# powermeting.net
KiCad netlist of a schematic drawn in EAGLE
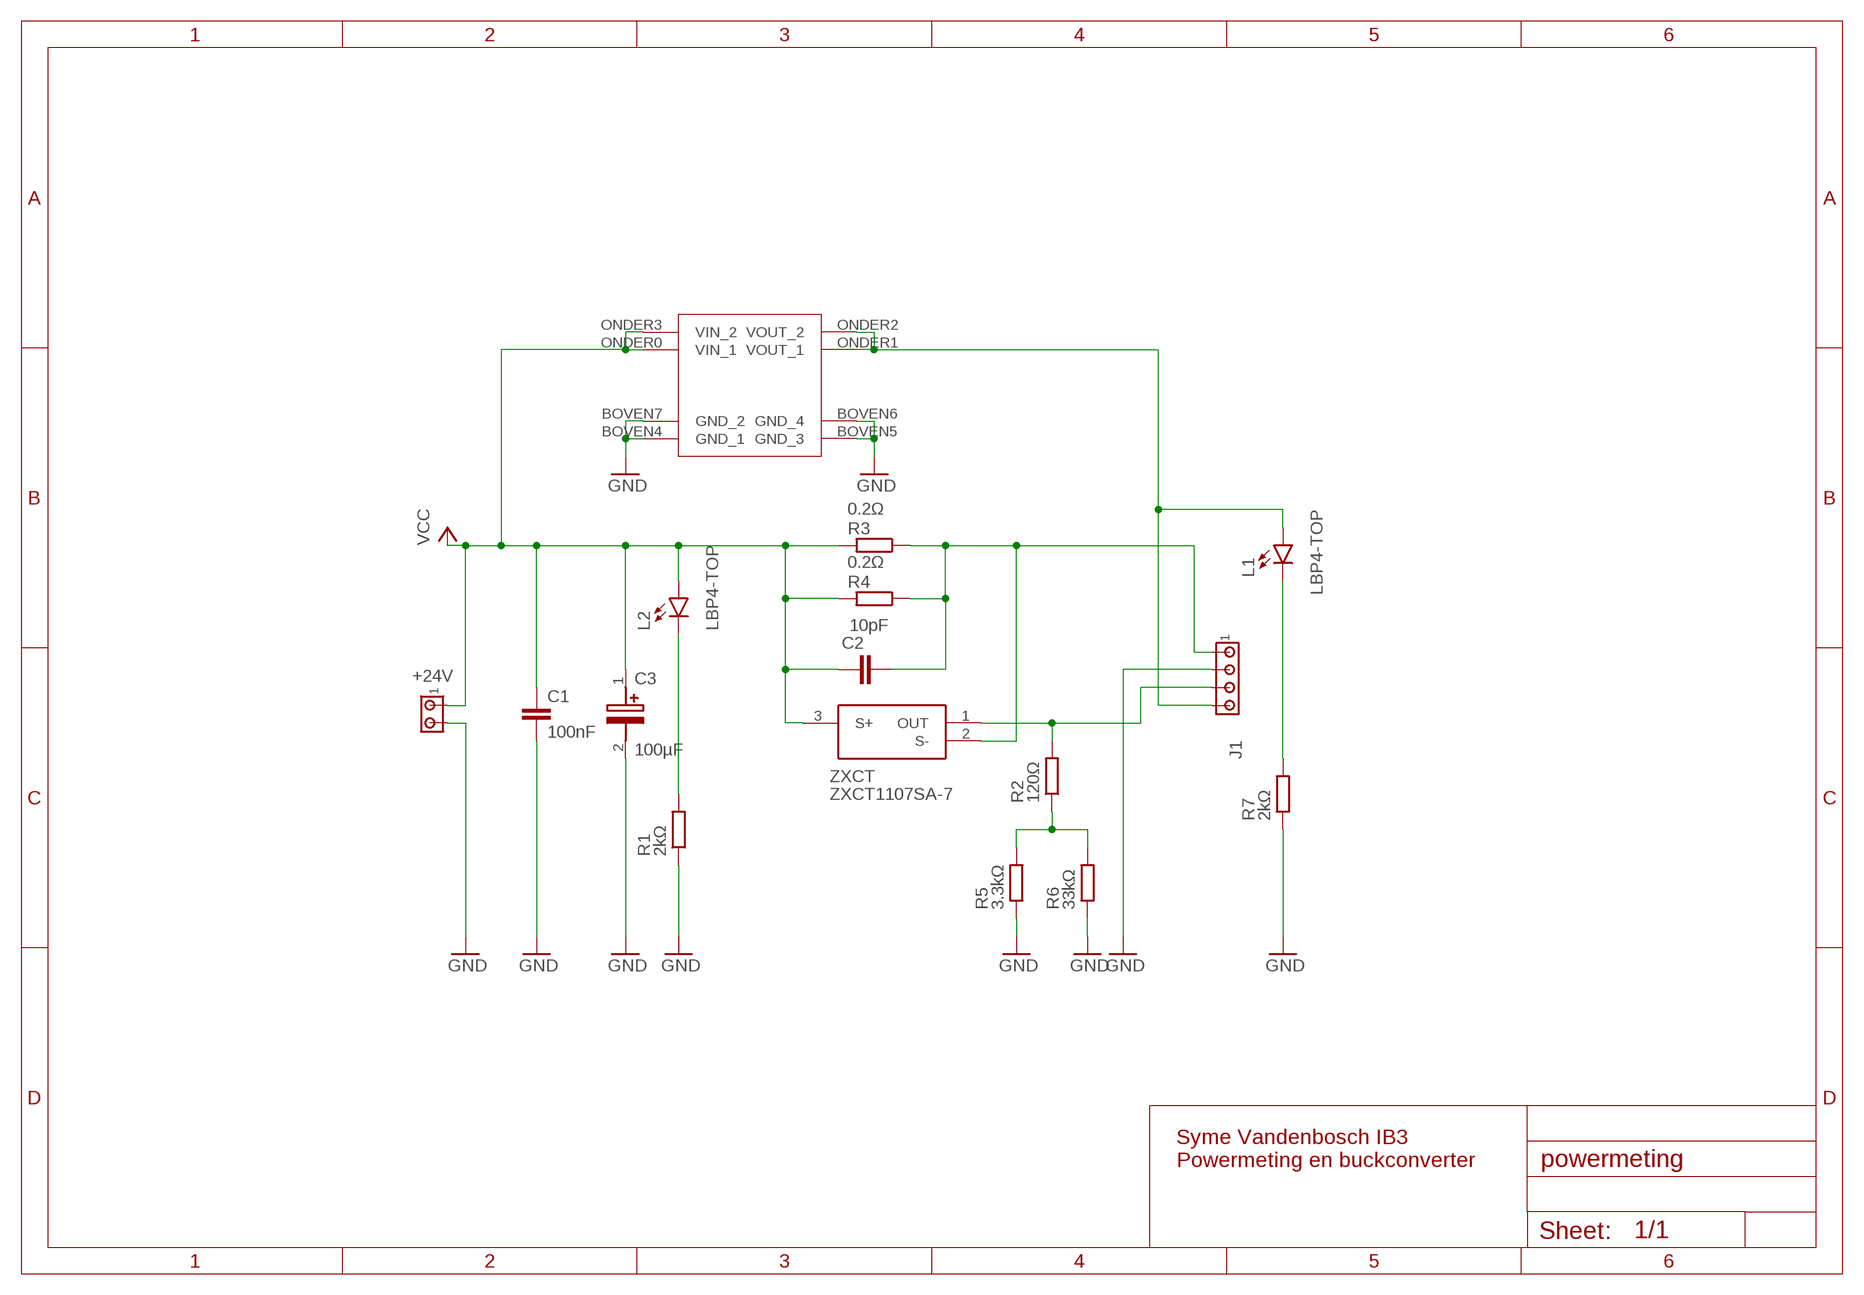
[diagram p0: schematic, sheet 1]

(export (version "E")
  (design (tool "Eeschema 10.0.6"))
  (components
    (comp (ref "+24V")
      (value "MTA02-100")
      (footprint "eagle-import:10X02MTA")
      (libsource (lib "eagle-import") (part "MTA02-100"))
    )
    (comp (ref "C1")
      (value "100nF")
      (footprint "eagle-import:C0805K")
      (libsource (lib "eagle-import") (part "C-EUC0805K"))
    )
    (comp (ref "C2")
      (value "10pF")
      (footprint "eagle-import:C0805K")
      (libsource (lib "eagle-import") (part "C-EUC0805K"))
    )
    (comp (ref "C3")
      (value "100µF")
      (footprint "eagle-import:EEHZA1H100R")
      (fields
        (field (name "ARROW_PART_NUMBER") "EEH-ZA1H100R")
        (field (name "MOUSER_PART_NUMBER") "667-EEH-ZA1H100R")
      )
      (libsource (lib "eagle-import") (part "EEH-ZA1H100R"))
    )
    (comp (ref "J1")
      (value "MTA04-100")
      (footprint "eagle-import:10X04MTA")
      (libsource (lib "eagle-import") (part "MTA04-100"))
    )
    (comp (ref "L1")
      (value "LBP4-TOP")
      (footprint "eagle-import:LED3MM")
      (libsource (lib "eagle-import") (part "LED3MM"))
    )
    (comp (ref "L2")
      (value "LBP4-TOP")
      (footprint "eagle-import:LED3MM")
      (libsource (lib "eagle-import") (part "LED3MM"))
    )
    (comp (ref "R1")
      (value "2kΩ")
      (footprint "eagle-import:M0805")
      (libsource (lib "eagle-import") (part "R-EU_M0805"))
    )
    (comp (ref "R2")
      (value "120Ω")
      (footprint "eagle-import:M0805")
      (libsource (lib "eagle-import") (part "R-EU_M0805"))
    )
    (comp (ref "R3")
      (value "0.2Ω")
      (footprint "eagle-import:M1206")
      (libsource (lib "eagle-import") (part "R-EU_M1206"))
    )
    (comp (ref "R4")
      (value "0.2Ω")
      (footprint "eagle-import:M1206")
      (libsource (lib "eagle-import") (part "R-EU_M1206"))
    )
    (comp (ref "R5")
      (value "3.3kΩ")
      (footprint "eagle-import:M0805")
      (libsource (lib "eagle-import") (part "R-EU_M0805"))
    )
    (comp (ref "R6")
      (value "33kΩ")
      (footprint "eagle-import:M0805")
      (libsource (lib "eagle-import") (part "R-EU_M0805"))
    )
    (comp (ref "R7")
      (value "2kΩ")
      (footprint "eagle-import:M0805")
      (libsource (lib "eagle-import") (part "R-EU_M0805"))
    )
    (comp (ref "U$1")
      (value "BUCK")
      (footprint "eagle-import:BUCK")
      (libsource (lib "eagle-import") (part "BUCK"))
    )
    (comp (ref "ZXCT")
      (value "ZXCT1107SA-7")
      (footprint "eagle-import:SOT96P240X110-3N")
      (fields (field (name "MOUSER_PART_NUMBER") "522-ZXCT1107SA-7"))
      (libsource (lib "eagle-import") (part "ZXCT1107SA-7"))
    )
  )
  (nets
    (net (code "1") (name "GND") (class "Default")
      (node (ref "+24V") (pin "2") (pinfunction "2_2") (pintype "passive"))
      (node (ref "C1") (pin "2") (pinfunction "2_2") (pintype "passive"))
      (node (ref "C3") (pin "2") (pinfunction "-_2") (pintype "bidirectional"))
      (node (ref "J1") (pin "2") (pinfunction "2_2") (pintype "passive"))
      (node (ref "R1") (pin "1") (pinfunction "1_1") (pintype "passive"))
      (node (ref "R5") (pin "1") (pinfunction "1_1") (pintype "passive"))
      (node (ref "R6") (pin "1") (pinfunction "1_1") (pintype "passive"))
      (node (ref "R7") (pin "1") (pinfunction "1_1") (pintype "passive"))
      (node (ref "U$1") (pin "BOVEN4") (pinfunction "GND_1_BOVEN4") (pintype "bidirectional"))
      (node (ref "U$1") (pin "BOVEN5") (pinfunction "GND_3_BOVEN5") (pintype "bidirectional"))
      (node (ref "U$1") (pin "BOVEN6") (pinfunction "GND_4_BOVEN6") (pintype "bidirectional"))
      (node (ref "U$1") (pin "BOVEN7") (pinfunction "GND_2_BOVEN7") (pintype "bidirectional"))
    )
    (net (code "2") (name "Net-(L1-C)") (class "Default")
      (node (ref "L1") (pin "K") (pinfunction "C_K") (pintype "passive"))
      (node (ref "R7") (pin "2") (pinfunction "2_2") (pintype "passive"))
    )
    (net (code "3") (name "Net-(L2-C)") (class "Default")
      (node (ref "L2") (pin "K") (pinfunction "C_K") (pintype "passive"))
      (node (ref "R1") (pin "2") (pinfunction "2_2") (pintype "passive"))
    )
    (net (code "4") (name "Net-(R2-Pad1)") (class "Default")
      (node (ref "R2") (pin "1") (pinfunction "1_1") (pintype "passive"))
      (node (ref "R5") (pin "2") (pinfunction "2_2") (pintype "passive"))
      (node (ref "R6") (pin "2") (pinfunction "2_2") (pintype "passive"))
    )
    (net (code "5") (name "Net-(U$1-VOUT_1)") (class "Default")
      (node (ref "J1") (pin "4") (pinfunction "4_4") (pintype "passive"))
      (node (ref "L1") (pin "A") (pinfunction "A_A") (pintype "passive"))
      (node (ref "U$1") (pin "ONDER1") (pinfunction "VOUT_1_ONDER1") (pintype "bidirectional"))
      (node (ref "U$1") (pin "ONDER2") (pinfunction "VOUT_2_ONDER2") (pintype "bidirectional"))
    )
    (net (code "6") (name "Net-(ZXCT-OUT)") (class "Default")
      (node (ref "J1") (pin "3") (pinfunction "3_3") (pintype "passive"))
      (node (ref "R2") (pin "2") (pinfunction "2_2") (pintype "passive"))
      (node (ref "ZXCT") (pin "1") (pinfunction "OUT_1") (pintype "bidirectional"))
    )
    (net (code "7") (name "Net-(ZXCT-S-)") (class "Default")
      (node (ref "C2") (pin "2") (pinfunction "2_2") (pintype "passive"))
      (node (ref "J1") (pin "1") (pinfunction "1_1") (pintype "passive"))
      (node (ref "R3") (pin "1") (pinfunction "1_1") (pintype "passive"))
      (node (ref "R4") (pin "1") (pinfunction "1_1") (pintype "passive"))
      (node (ref "ZXCT") (pin "2") (pinfunction "S-_2") (pintype "bidirectional"))
    )
    (net (code "8") (name "VCC") (class "Default")
      (node (ref "+24V") (pin "1") (pinfunction "1_1") (pintype "passive"))
      (node (ref "C1") (pin "1") (pinfunction "1_1") (pintype "passive"))
      (node (ref "C2") (pin "1") (pinfunction "1_1") (pintype "passive"))
      (node (ref "C3") (pin "1") (pinfunction "+_1") (pintype "bidirectional"))
      (node (ref "L2") (pin "A") (pinfunction "A_A") (pintype "passive"))
      (node (ref "R3") (pin "2") (pinfunction "2_2") (pintype "passive"))
      (node (ref "R4") (pin "2") (pinfunction "2_2") (pintype "passive"))
      (node (ref "U$1") (pin "ONDER0") (pinfunction "VIN_1_ONDER0") (pintype "bidirectional"))
      (node (ref "U$1") (pin "ONDER3") (pinfunction "VIN_2_ONDER3") (pintype "bidirectional"))
      (node (ref "ZXCT") (pin "3") (pinfunction "S+_3") (pintype "bidirectional"))
    )
  )
)
